# POWER.net
KiCad netlist of a schematic drawn in Altium Designer
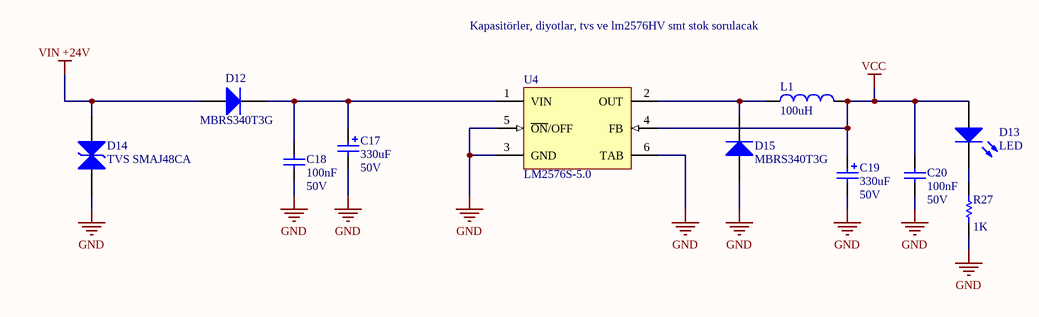
[diagram p0: POWER.SchDoc]

(export (version "E")
  (design (tool "Eeschema 10.0.6"))
  (components
    (comp (ref "C17")
      (value "330uF")
      (footprint "CAP Size H13= 12.5x13.8mm")
      (description "Polarized Capacitor (Radial)")
      (fields
        (field (name "VOLTAGE") "50V")
        (field (name "Comment") "Cap Pol1")
        (field (name "PUBLISHER") "Altium Limited")
      )
      (libsource (lib "Erdem_05112012") (part "Cap Pol1"))
    )
    (comp (ref "C18")
      (value "100nF")
      (footprint "3-0603_L")
      (description "Capacitor")
      (fields
        (field (name "VOLTAGE") "50V")
        (field (name "Comment") "Cap")
        (field (name "PUBLISHER") "Altium Limited")
      )
      (libsource (lib "Erdem_05112012") (part "Cap"))
    )
    (comp (ref "C19")
      (value "330uF")
      (footprint "CAP Size H13= 12.5x13.8mm")
      (description "Polarized Capacitor (Radial)")
      (fields
        (field (name "VOLTAGE") "50V")
        (field (name "Comment") "Cap Pol1")
        (field (name "PUBLISHER") "Altium Limited")
      )
      (libsource (lib "Erdem_05112012") (part "Cap Pol1"))
    )
    (comp (ref "C20")
      (value "100nF")
      (footprint "3-0603_L")
      (description "Capacitor")
      (fields
        (field (name "VOLTAGE") "50V")
        (field (name "Comment") "Cap")
        (field (name "PUBLISHER") "Altium Limited")
      )
      (libsource (lib "Erdem_05112012") (part "Cap"))
    )
    (comp (ref "D12")
      (value "MBRS340T3G")
      (footprint "CASE 403-03 ISSUE E")
      (description "3 Amp Shotky Rectifier")
      (fields (field (name "PUBLISHER") "Altium Limited"))
      (libsource (lib "Erdem_05112012") (part "MBRS340T3G"))
    )
    (comp (ref "D13")
      (value "LED")
      (footprint "6-0805 - LED")
      (description "Typical INFRARED GaAs LED")
      (fields (field (name "PUBLISHER") "Altium Limited"))
      (libsource (lib "Erdem_05112012") (part "LED"))
    )
    (comp (ref "D14")
      (value "TVS SMAJ48CA")
      (footprint "DO214 AA")
      (fields (field (name "PUBLISHER") "Altium Limited"))
      (libsource (lib "Erdem_05112012") (part "TVS SMAJ48CA"))
    )
    (comp (ref "D15")
      (value "MBRS340T3G")
      (footprint "CASE 403-03 ISSUE E")
      (description "3 Amp Shotky Rectifier")
      (fields (field (name "PUBLISHER") "Altium Limited"))
      (libsource (lib "Erdem_05112012") (part "MBRS340T3G"))
    )
    (comp (ref "L1")
      (value "100uH")
      (footprint "EB-221M18G01")
      (description "Inductor")
      (fields (field (name "PUBLISHER") "Altium Limited"))
      (libsource (lib "Erdem_05112012") (part "Inductor"))
    )
    (comp (ref "R27")
      (value "1K")
      (footprint "6-0805_M")
      (description "Resistor")
      (fields (field (name "Comment") "Res1") (field (name "PUBLISHER") "Altium Limited"))
      (libsource (lib "Erdem_05112012") (part "Res1"))
    )
    (comp (ref "U4")
      (value "LM2576S-5.0")
      (footprint "TS5B_M")
      (description "SIMPLE SWITCHER; 3A Step-Down Voltage Regulator")
      (fields
        (field (name "MANUFACTURER") "National Semiconductor")
        (field (name "DIGIKEYPARTNUMBER") "LM2576S-5.0-ND")
        (field (name "PUBLISHER") "Altium Limited")
      )
      (libsource (lib "Erdem_05112012") (part "LM2576S-5.0"))
    )
  )
  (nets
    (net (code "1") (name "GND") (class "Default")
      (node (ref "C17") (pin "2") (pinfunction "2_2") (pintype "passive"))
      (node (ref "C18") (pin "1") (pinfunction "1_1") (pintype "passive"))
      (node (ref "C19") (pin "2") (pinfunction "2_2") (pintype "passive"))
      (node (ref "C20") (pin "1") (pinfunction "1_1") (pintype "passive"))
      (node (ref "D14") (pin "1") (pinfunction "1_1") (pintype "passive"))
      (node (ref "D15") (pin "1") (pinfunction "A_1") (pintype "passive"))
      (node (ref "R27") (pin "1") (pinfunction "1_1") (pintype "passive"))
      (node (ref "U4") (pin "3") (pinfunction "GND_3") (pintype "power_in"))
      (node (ref "U4") (pin "5") (pinfunction "~{ON}/OFF_5") (pintype "input"))
      (node (ref "U4") (pin "6") (pinfunction "TAB_6") (pintype "power_in"))
    )
    (net (code "2") (name "Net-(D12-K)") (class "Default")
      (node (ref "C17") (pin "1") (pinfunction "1_1") (pintype "passive"))
      (node (ref "C18") (pin "2") (pinfunction "2_2") (pintype "passive"))
      (node (ref "D12") (pin "2") (pinfunction "K_2") (pintype "passive"))
      (node (ref "U4") (pin "1") (pinfunction "VIN_1") (pintype "power_in"))
    )
    (net (code "3") (name "Net-(D13-K)") (class "Default")
      (node (ref "D13") (pin "2") (pinfunction "K_2") (pintype "passive"))
      (node (ref "R27") (pin "2") (pinfunction "2_2") (pintype "passive"))
    )
    (net (code "4") (name "Net-(D15-K)") (class "Default")
      (node (ref "D15") (pin "2") (pinfunction "K_2") (pintype "passive"))
      (node (ref "L1") (pin "1") (pinfunction "1_1") (pintype "passive"))
      (node (ref "U4") (pin "2") (pinfunction "OUT_2") (pintype "power_in"))
    )
    (net (code "5") (name "VCC") (class "Default")
      (node (ref "C19") (pin "1") (pinfunction "1_1") (pintype "passive"))
      (node (ref "C20") (pin "2") (pinfunction "2_2") (pintype "passive"))
      (node (ref "D13") (pin "1") (pinfunction "A_1") (pintype "passive"))
      (node (ref "L1") (pin "2") (pinfunction "2_2") (pintype "passive"))
      (node (ref "U4") (pin "4") (pinfunction "FB_4") (pintype "input"))
    )
    (net (code "6") (name "VIN +24V") (class "Default")
      (node (ref "D12") (pin "1") (pinfunction "A_1") (pintype "passive"))
      (node (ref "D14") (pin "2") (pinfunction "2_2") (pintype "passive"))
    )
  )
)
